# Sheet1.net
KiCad netlist of a schematic drawn in Altium Designer
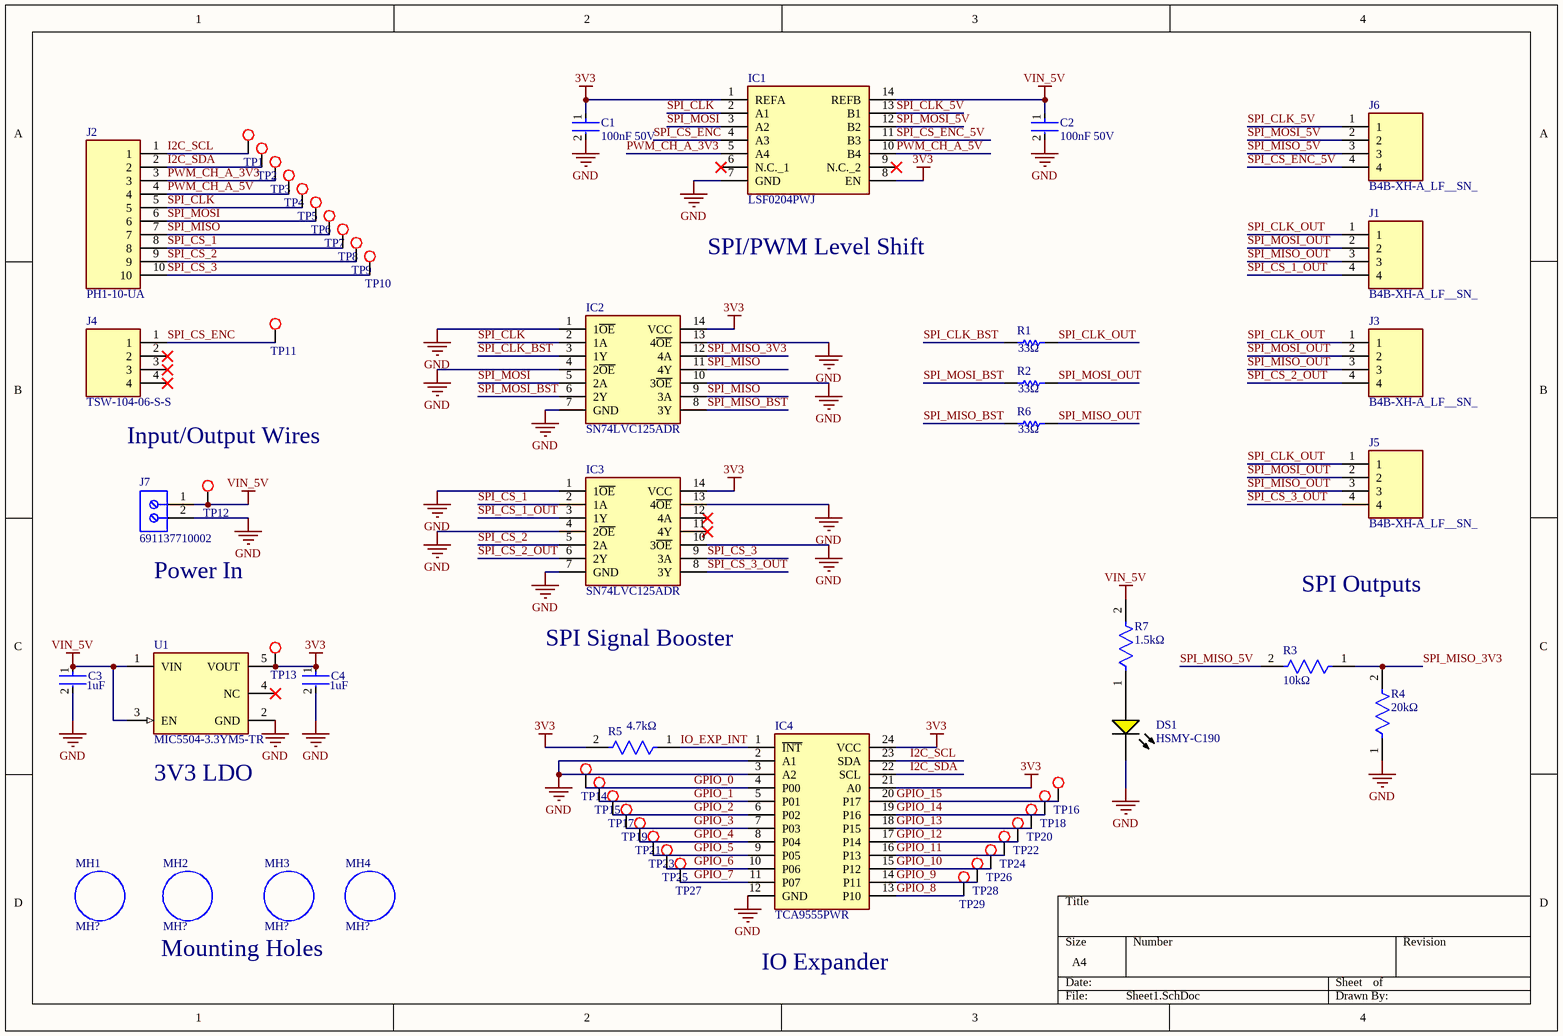
[diagram p0: Sheet1.SchDoc]

(export (version "E")
  (design (tool "Eeschema 10.0.6"))
  (components
    (comp (ref "C1")
      (value "100nF 50V")
      (footprint "FP-CL31-IPC_C")
      (description "Cap Ceramic 100nF 50V X7R ±10% SMD 1206 +125°C Embossed T/R")
      (fields (field (name "TOLERANCE") "10%"))
      (libsource (lib "Altium Content Vault") (part "b4654b650e69147ec39a6b967a45e02"))
    )
    (comp (ref "C2")
      (value "100nF 50V")
      (footprint "FP-CL31-IPC_C")
      (description "Cap Ceramic 100nF 50V X7R ±10% SMD 1206 +125°C Embossed T/R")
      (fields (field (name "TOLERANCE") "10%"))
      (libsource (lib "Altium Content Vault") (part "b4654b650e69147ec39a6b967a45e02"))
    )
    (comp (ref "C3")
      (value "1uF")
      (footprint "FP-CL10-IPC_C")
      (description "Cap Ceramic 1uF 10V X5R ±10% Pad SMD 0603 +85°C T/R")
      (fields (field (name "VOLTAGE") "10V") (field (name "TOLERANCE") "10%"))
      (libsource (lib "Altium Content Vault") (part "b4654b650e69147ec39a6b967a45e02"))
    )
    (comp (ref "C4")
      (value "1uF")
      (footprint "FP-CL10-IPC_C")
      (description "Cap Ceramic 1uF 10V X5R ±10% Pad SMD 0603 +85°C T/R")
      (fields (field (name "VOLTAGE") "10V") (field (name "TOLERANCE") "10%"))
      (libsource (lib "Altium Content Vault") (part "b4654b650e69147ec39a6b967a45e02"))
    )
    (comp (ref "DS1")
      (value "HSMY-C190")
      (footprint "AVAG-HSMX-C190_V")
      (description "LED Uni-Color Yellow, 65 mW, 20 mA, -40 to 85 degC, 2-Pin SMD, RoHS, Tape and Reel")
      (fields (field (name "TOLERANCE") "1%"))
      (libsource (lib "Altium Content Vault") (part "LED-YELLOW-AK-2"))
    )
    (comp (ref "IC1")
      (value "LSF0204PWJ")
      (footprint "SamacSys:SOP65P640X110-14N")
      (description "Integrated Circuit")
      (fields (field (name "MOUSER PART NUMBER") "771-LSF0204PWJ"))
      (libsource (lib "*") (part "LSF0204PWJ"))
    )
    (comp (ref "IC2")
      (value "SN74LVC125ADR")
      (footprint "SamacSys:SOIC127P600X175-14N")
      (description "Integrated Circuit")
      (fields (field (name "MOUSER PART NUMBER") "595-SN74LVC125ADR"))
      (libsource (lib "*") (part "SN74LVC125ADR"))
    )
    (comp (ref "IC3")
      (value "SN74LVC125ADR")
      (footprint "SamacSys:SOIC127P600X175-14N")
      (description "Integrated Circuit")
      (fields (field (name "MOUSER PART NUMBER") "595-SN74LVC125ADR"))
      (libsource (lib "*") (part "SN74LVC125ADR"))
    )
    (comp (ref "IC4")
      (value "TCA9555PWR")
      (footprint "SamacSys:SOP65P640X120-24N")
      (description "Integrated Circuit")
      (fields (field (name "MOUSER PART NUMBER") "595-TCA9555PWR"))
      (libsource (lib "*") (part "TCA9555PWR"))
    )
    (comp (ref "J1")
      (value "B4B-XH-A_LF__SN_")
      (footprint "SamacSys:B4BXHALFSN")
      (description "Connector")
      (fields
        (field (name "MANUFACTURER_PART_NUMBER") "B4B-XH-A(LF)(SN)")
        (field (name "MOUSER PART NUMBER") "306-B4BXHALFSN")
      )
      (libsource (lib "*") (part "B4B-XH-A_LF__SN_"))
    )
    (comp (ref "J2")
      (value "PH1-10-UA")
      (footprint "SamacSys:HDRV10W64P0X254_1X10_2540X249X886P")
      (description "Connector")
      (fields (field (name "MOUSER PART NUMBER") "737-PH1-10-UA"))
      (libsource (lib "*") (part "PH1-10-UA"))
    )
    (comp (ref "J3")
      (value "B4B-XH-A_LF__SN_")
      (footprint "SamacSys:B4BXHALFSN")
      (description "Connector")
      (fields
        (field (name "MANUFACTURER_PART_NUMBER") "B4B-XH-A(LF)(SN)")
        (field (name "MOUSER PART NUMBER") "306-B4BXHALFSN")
      )
      (libsource (lib "*") (part "B4B-XH-A_LF__SN_"))
    )
    (comp (ref "J4")
      (value "TSW-104-06-S-S")
      (footprint "SamacSys:TSW-104-XX-YY-S")
      (description "Connector")
      (libsource (lib "*") (part "TSW-104-06-S-S"))
    )
    (comp (ref "J5")
      (value "B4B-XH-A_LF__SN_")
      (footprint "SamacSys:B4BXHALFSN")
      (description "Connector")
      (fields
        (field (name "MANUFACTURER_PART_NUMBER") "B4B-XH-A(LF)(SN)")
        (field (name "MOUSER PART NUMBER") "306-B4BXHALFSN")
      )
      (libsource (lib "*") (part "B4B-XH-A_LF__SN_"))
    )
    (comp (ref "J6")
      (value "B4B-XH-A_LF__SN_")
      (footprint "SamacSys:B4BXHALFSN")
      (description "Connector")
      (fields
        (field (name "MANUFACTURER_PART_NUMBER") "B4B-XH-A(LF)(SN)")
        (field (name "MOUSER PART NUMBER") "306-B4BXHALFSN")
      )
      (libsource (lib "*") (part "B4B-XH-A_LF__SN_"))
    )
    (comp (ref "J7")
      (value "691137710002")
      (footprint "691137710002")
      (libsource (lib "Altium Content Vault") (part "TBL - 1R - 02P - Screw"))
    )
    (comp (ref "MH1")
      (value "MH?")
      (footprint "Mounting Hole")
      (libsource (lib "Schlib1") (part "Mounting Hole"))
    )
    (comp (ref "MH2")
      (value "MH?")
      (footprint "Mounting Hole")
      (libsource (lib "Schlib1") (part "Mounting Hole"))
    )
    (comp (ref "MH3")
      (value "MH?")
      (footprint "Mounting Hole")
      (libsource (lib "Schlib1") (part "Mounting Hole"))
    )
    (comp (ref "MH4")
      (value "MH?")
      (footprint "Mounting Hole")
      (libsource (lib "Schlib1") (part "Mounting Hole"))
    )
    (comp (ref "R1")
      (value "33Ω")
      (footprint "RESC1609X50X30NL10T20")
      (fields (field (name "MANUFACTURER") "Vishay Dale") (field (name "PART NUMBER") "CRCW060333R0JNTA"))
      (libsource (lib "Altium Content Vault") (part "RES"))
    )
    (comp (ref "R2")
      (value "33Ω")
      (footprint "RESC1609X50X30NL10T20")
      (fields (field (name "MANUFACTURER") "Vishay Dale") (field (name "PART NUMBER") "CRCW060333R0JNTA"))
      (libsource (lib "Altium Content Vault") (part "RES"))
    )
    (comp (ref "R3")
      (value "10kΩ")
      (footprint "FP-RT0603-MFG")
      (description "RES SMD 10K OHM 0.1% 1/10W 0603")
      (fields
        (field (name "TOLERANCE") "0.001")
        (field (name "OCTOPART") "https://octopart.com/rt0603bre0710kl-yageo-1273959")
      )
      (libsource (lib "Altium Content Vault") (part "1029c3af85768c4190bb7ad29bc67b5"))
    )
    (comp (ref "R4")
      (value "20kΩ")
      (footprint "FP-RT0805-MFG")
      (description "RES SMD 20K OHM 1% 1/8W 0805")
      (fields
        (field (name "MANUFACTURER") "Yageo")
        (field (name "MANUFACTURER PART NUMBER") "RT0805FRE0720KL")
      )
      (libsource (lib "Altium Content Vault") (part "1029c3af85768c4190bb7ad29bc67b5"))
    )
    (comp (ref "R5")
      (value "4.7kΩ")
      (footprint "FP-RT0805-MFG")
      (description "RES SMD 4.7K OHM 1% 1/8W 0805")
      (fields (field (name "TOLERANCE") "0.0001") (field (name "MANUFACTURER PART NUMBER") "RT0805FRE074K7L"))
      (libsource (lib "Altium Content Vault") (part "1029c3af85768c4190bb7ad29bc67b5"))
    )
    (comp (ref "R6")
      (value "33Ω")
      (footprint "RESC1609X50X30NL10T20")
      (fields (field (name "MANUFACTURER") "Vishay Dale") (field (name "PART NUMBER") "CRCW060333R0JNTA"))
      (libsource (lib "Altium Content Vault") (part "RES"))
    )
    (comp (ref "R7")
      (value "1.5kΩ")
      (footprint "FP-RC1608-IPC_B")
      (description "Res Thick Film 0603 1.5kΩ 1% 0.1W ±100ppm/°C Molded SMD T/R")
      (fields (field (name "TOLERANCE") "1%"))
      (libsource (lib "Altium Content Vault") (part "1029c3af85768c4190bb7ad29bc67b5"))
    )
    (comp (ref "TP1") (value "TP") (footprint "Testpoint") (libsource (lib "Schlib1") (part "Testpoint")))
    (comp (ref "TP2") (value "TP") (footprint "Testpoint") (libsource (lib "Schlib1") (part "Testpoint")))
    (comp (ref "TP3") (value "TP") (footprint "Testpoint") (libsource (lib "Schlib1") (part "Testpoint")))
    (comp (ref "TP4") (value "TP") (footprint "Testpoint") (libsource (lib "Schlib1") (part "Testpoint")))
    (comp (ref "TP5") (value "TP") (footprint "Testpoint") (libsource (lib "Schlib1") (part "Testpoint")))
    (comp (ref "TP6") (value "TP") (footprint "Testpoint") (libsource (lib "Schlib1") (part "Testpoint")))
    (comp (ref "TP7") (value "TP") (footprint "Testpoint") (libsource (lib "Schlib1") (part "Testpoint")))
    (comp (ref "TP8") (value "TP") (footprint "Testpoint") (libsource (lib "Schlib1") (part "Testpoint")))
    (comp (ref "TP9") (value "TP") (footprint "Testpoint") (libsource (lib "Schlib1") (part "Testpoint")))
    (comp (ref "TP10") (value "TP") (footprint "Testpoint") (libsource (lib "Schlib1") (part "Testpoint")))
    (comp (ref "TP11") (value "TP") (footprint "Testpoint") (libsource (lib "Schlib1") (part "Testpoint")))
    (comp (ref "TP12") (value "TP") (footprint "Testpoint") (libsource (lib "Schlib1") (part "Testpoint")))
    (comp (ref "TP13") (value "TP") (footprint "Testpoint") (libsource (lib "Schlib1") (part "Testpoint")))
    (comp (ref "TP14") (value "TP") (footprint "Testpoint") (libsource (lib "Schlib1") (part "Testpoint")))
    (comp (ref "TP15") (value "TP") (footprint "Testpoint") (libsource (lib "Schlib1") (part "Testpoint")))
    (comp (ref "TP16") (value "TP") (footprint "Testpoint") (libsource (lib "Schlib1") (part "Testpoint")))
    (comp (ref "TP17") (value "TP") (footprint "Testpoint") (libsource (lib "Schlib1") (part "Testpoint")))
    (comp (ref "TP18") (value "TP") (footprint "Testpoint") (libsource (lib "Schlib1") (part "Testpoint")))
    (comp (ref "TP19") (value "TP") (footprint "Testpoint") (libsource (lib "Schlib1") (part "Testpoint")))
    (comp (ref "TP20") (value "TP") (footprint "Testpoint") (libsource (lib "Schlib1") (part "Testpoint")))
    (comp (ref "TP21") (value "TP") (footprint "Testpoint") (libsource (lib "Schlib1") (part "Testpoint")))
    (comp (ref "TP22") (value "TP") (footprint "Testpoint") (libsource (lib "Schlib1") (part "Testpoint")))
    (comp (ref "TP23") (value "TP") (footprint "Testpoint") (libsource (lib "Schlib1") (part "Testpoint")))
    (comp (ref "TP24") (value "TP") (footprint "Testpoint") (libsource (lib "Schlib1") (part "Testpoint")))
    (comp (ref "TP25") (value "TP") (footprint "Testpoint") (libsource (lib "Schlib1") (part "Testpoint")))
    (comp (ref "TP26") (value "TP") (footprint "Testpoint") (libsource (lib "Schlib1") (part "Testpoint")))
    (comp (ref "TP27") (value "TP") (footprint "Testpoint") (libsource (lib "Schlib1") (part "Testpoint")))
    (comp (ref "TP28") (value "TP") (footprint "Testpoint") (libsource (lib "Schlib1") (part "Testpoint")))
    (comp (ref "TP29") (value "TP") (footprint "Testpoint") (libsource (lib "Schlib1") (part "Testpoint")))
    (comp (ref "U1")
      (value "MIC5504-3.3YM5-TR")
      (footprint "FP-SOT23-5LD-PL-1-MFG")
      (description "IC REG LINEAR 3.3V 300MA SOT23-5")
      (libsource (lib "Altium Content Vault") (part "96048095611b4a9579e1e315950d302"))
    )
  )
  (nets
    (net (code "1") (name "/GPIO_0") (class "Default")
      (node (ref "IC4") (pin "4") (pinfunction "P00_4") (pintype "passive"))
      (node (ref "TP14") (pin "0") (pinfunction "0_0") (pintype "passive"))
    )
    (net (code "2") (name "/GPIO_1") (class "Default")
      (node (ref "IC4") (pin "5") (pinfunction "P01_5") (pintype "passive"))
      (node (ref "TP15") (pin "0") (pinfunction "0_0") (pintype "passive"))
    )
    (net (code "3") (name "/GPIO_2") (class "Default")
      (node (ref "IC4") (pin "6") (pinfunction "P02_6") (pintype "passive"))
      (node (ref "TP17") (pin "0") (pinfunction "0_0") (pintype "passive"))
    )
    (net (code "4") (name "/GPIO_3") (class "Default")
      (node (ref "IC4") (pin "7") (pinfunction "P03_7") (pintype "passive"))
      (node (ref "TP19") (pin "0") (pinfunction "0_0") (pintype "passive"))
    )
    (net (code "5") (name "/GPIO_4") (class "Default")
      (node (ref "IC4") (pin "8") (pinfunction "P04_8") (pintype "passive"))
      (node (ref "TP21") (pin "0") (pinfunction "0_0") (pintype "passive"))
    )
    (net (code "6") (name "/GPIO_5") (class "Default")
      (node (ref "IC4") (pin "9") (pinfunction "P05_9") (pintype "passive"))
      (node (ref "TP23") (pin "0") (pinfunction "0_0") (pintype "passive"))
    )
    (net (code "7") (name "/GPIO_6") (class "Default")
      (node (ref "IC4") (pin "10") (pinfunction "P06_10") (pintype "passive"))
      (node (ref "TP25") (pin "0") (pinfunction "0_0") (pintype "passive"))
    )
    (net (code "8") (name "/GPIO_7") (class "Default")
      (node (ref "IC4") (pin "11") (pinfunction "P07_11") (pintype "passive"))
      (node (ref "TP27") (pin "0") (pinfunction "0_0") (pintype "passive"))
    )
    (net (code "9") (name "/GPIO_8") (class "Default")
      (node (ref "IC4") (pin "13") (pinfunction "P10_13") (pintype "passive"))
      (node (ref "TP29") (pin "0") (pinfunction "0_0") (pintype "passive"))
    )
    (net (code "10") (name "/GPIO_9") (class "Default")
      (node (ref "IC4") (pin "14") (pinfunction "P11_14") (pintype "passive"))
      (node (ref "TP28") (pin "0") (pinfunction "0_0") (pintype "passive"))
    )
    (net (code "11") (name "/GPIO_10") (class "Default")
      (node (ref "IC4") (pin "15") (pinfunction "P12_15") (pintype "passive"))
      (node (ref "TP26") (pin "0") (pinfunction "0_0") (pintype "passive"))
    )
    (net (code "12") (name "/GPIO_11") (class "Default")
      (node (ref "IC4") (pin "16") (pinfunction "P13_16") (pintype "passive"))
      (node (ref "TP24") (pin "0") (pinfunction "0_0") (pintype "passive"))
    )
    (net (code "13") (name "/GPIO_12") (class "Default")
      (node (ref "IC4") (pin "17") (pinfunction "P14_17") (pintype "passive"))
      (node (ref "TP22") (pin "0") (pinfunction "0_0") (pintype "passive"))
    )
    (net (code "14") (name "/GPIO_13") (class "Default")
      (node (ref "IC4") (pin "18") (pinfunction "P15_18") (pintype "passive"))
      (node (ref "TP20") (pin "0") (pinfunction "0_0") (pintype "passive"))
    )
    (net (code "15") (name "/GPIO_14") (class "Default")
      (node (ref "IC4") (pin "19") (pinfunction "P16_19") (pintype "passive"))
      (node (ref "TP18") (pin "0") (pinfunction "0_0") (pintype "passive"))
    )
    (net (code "16") (name "/GPIO_15") (class "Default")
      (node (ref "IC4") (pin "20") (pinfunction "P17_20") (pintype "passive"))
      (node (ref "TP16") (pin "0") (pinfunction "0_0") (pintype "passive"))
    )
    (net (code "17") (name "/I2C_SCL") (class "Default")
      (node (ref "IC4") (pin "23") (pinfunction "SDA_23") (pintype "passive"))
      (node (ref "J2") (pin "1") (pinfunction "1_1") (pintype "passive"))
      (node (ref "TP1") (pin "0") (pinfunction "0_0") (pintype "passive"))
    )
    (net (code "18") (name "/I2C_SDA") (class "Default")
      (node (ref "IC4") (pin "22") (pinfunction "SCL_22") (pintype "passive"))
      (node (ref "J2") (pin "2") (pinfunction "2_2") (pintype "passive"))
      (node (ref "TP2") (pin "0") (pinfunction "0_0") (pintype "passive"))
    )
    (net (code "19") (name "/IO_EXP_INT") (class "Default")
      (node (ref "IC4") (pin "1") (pinfunction "~{INT}_1") (pintype "passive"))
      (node (ref "R5") (pin "1") (pinfunction "1_1") (pintype "passive"))
    )
    (net (code "20") (name "/PWM_CH_A_3V3") (class "Default")
      (node (ref "IC1") (pin "5") (pinfunction "A4_5") (pintype "passive"))
      (node (ref "J2") (pin "3") (pinfunction "3_3") (pintype "passive"))
      (node (ref "TP3") (pin "0") (pinfunction "0_0") (pintype "passive"))
    )
    (net (code "21") (name "/PWM_CH_A_5V") (class "Default")
      (node (ref "IC1") (pin "10") (pinfunction "B4_10") (pintype "passive"))
      (node (ref "J2") (pin "4") (pinfunction "4_4") (pintype "passive"))
      (node (ref "TP4") (pin "0") (pinfunction "0_0") (pintype "passive"))
    )
    (net (code "22") (name "/SPI_CLK") (class "Default")
      (node (ref "IC1") (pin "2") (pinfunction "A1_2") (pintype "passive"))
      (node (ref "IC2") (pin "2") (pinfunction "1A_2") (pintype "passive"))
      (node (ref "J2") (pin "5") (pinfunction "5_5") (pintype "passive"))
      (node (ref "TP5") (pin "0") (pinfunction "0_0") (pintype "passive"))
    )
    (net (code "23") (name "/SPI_CLK_5V") (class "Default")
      (node (ref "IC1") (pin "13") (pinfunction "B1_13") (pintype "passive"))
      (node (ref "J6") (pin "1") (pinfunction "1_1") (pintype "passive"))
    )
    (net (code "24") (name "/SPI_CLK_BST") (class "Default")
      (node (ref "IC2") (pin "3") (pinfunction "1Y_3") (pintype "passive"))
      (node (ref "R1") (pin "1") (pinfunction "1_1") (pintype "passive"))
    )
    (net (code "25") (name "/SPI_CLK_OUT") (class "Default")
      (node (ref "J1") (pin "1") (pinfunction "1_1") (pintype "passive"))
      (node (ref "J3") (pin "1") (pinfunction "1_1") (pintype "passive"))
      (node (ref "J5") (pin "1") (pinfunction "1_1") (pintype "passive"))
      (node (ref "R1") (pin "2") (pinfunction "2_2") (pintype "passive"))
    )
    (net (code "26") (name "/SPI_CS_1") (class "Default")
      (node (ref "IC3") (pin "2") (pinfunction "1A_2") (pintype "passive"))
      (node (ref "J2") (pin "8") (pinfunction "8_8") (pintype "passive"))
      (node (ref "TP8") (pin "0") (pinfunction "0_0") (pintype "passive"))
    )
    (net (code "27") (name "/SPI_CS_1_OUT") (class "Default")
      (node (ref "IC3") (pin "3") (pinfunction "1Y_3") (pintype "passive"))
      (node (ref "J1") (pin "4") (pinfunction "4_4") (pintype "passive"))
    )
    (net (code "28") (name "/SPI_CS_2") (class "Default")
      (node (ref "IC3") (pin "5") (pinfunction "2A_5") (pintype "passive"))
      (node (ref "J2") (pin "9") (pinfunction "9_9") (pintype "passive"))
      (node (ref "TP9") (pin "0") (pinfunction "0_0") (pintype "passive"))
    )
    (net (code "29") (name "/SPI_CS_2_OUT") (class "Default")
      (node (ref "IC3") (pin "6") (pinfunction "2Y_6") (pintype "passive"))
      (node (ref "J3") (pin "4") (pinfunction "4_4") (pintype "passive"))
    )
    (net (code "30") (name "/SPI_CS_3") (class "Default")
      (node (ref "IC3") (pin "9") (pinfunction "3A_9") (pintype "passive"))
      (node (ref "J2") (pin "10") (pinfunction "10_10") (pintype "passive"))
      (node (ref "TP10") (pin "0") (pinfunction "0_0") (pintype "passive"))
    )
    (net (code "31") (name "/SPI_CS_3_OUT") (class "Default")
      (node (ref "IC3") (pin "8") (pinfunction "3Y_8") (pintype "passive"))
      (node (ref "J5") (pin "4") (pinfunction "4_4") (pintype "passive"))
    )
    (net (code "32") (name "/SPI_CS_ENC") (class "Default")
      (node (ref "IC1") (pin "4") (pinfunction "A3_4") (pintype "passive"))
      (node (ref "J4") (pin "1") (pinfunction "1_1") (pintype "passive"))
      (node (ref "TP11") (pin "0") (pinfunction "0_0") (pintype "passive"))
    )
    (net (code "33") (name "/SPI_CS_ENC_5V") (class "Default")
      (node (ref "IC1") (pin "11") (pinfunction "B3_11") (pintype "passive"))
      (node (ref "J6") (pin "4") (pinfunction "4_4") (pintype "passive"))
    )
    (net (code "34") (name "/SPI_MISO") (class "Default")
      (node (ref "IC2") (pin "11") (pinfunction "4Y_11") (pintype "passive"))
      (node (ref "IC2") (pin "9") (pinfunction "3A_9") (pintype "passive"))
      (node (ref "J2") (pin "7") (pinfunction "7_7") (pintype "passive"))
      (node (ref "TP7") (pin "0") (pinfunction "0_0") (pintype "passive"))
    )
    (net (code "35") (name "/SPI_MISO_3V3") (class "Default")
      (node (ref "IC2") (pin "12") (pinfunction "4A_12") (pintype "passive"))
      (node (ref "R3") (pin "1") (pinfunction "1_1") (pintype "passive"))
      (node (ref "R4") (pin "2") (pinfunction "2_2") (pintype "passive"))
    )
    (net (code "36") (name "/SPI_MISO_5V") (class "Default")
      (node (ref "J6") (pin "3") (pinfunction "3_3") (pintype "passive"))
      (node (ref "R3") (pin "2") (pinfunction "2_2") (pintype "passive"))
    )
    (net (code "37") (name "/SPI_MISO_BST") (class "Default")
      (node (ref "IC2") (pin "8") (pinfunction "3Y_8") (pintype "passive"))
      (node (ref "R6") (pin "1") (pinfunction "1_1") (pintype "passive"))
    )
    (net (code "38") (name "/SPI_MISO_OUT") (class "Default")
      (node (ref "J1") (pin "3") (pinfunction "3_3") (pintype "passive"))
      (node (ref "J3") (pin "3") (pinfunction "3_3") (pintype "passive"))
      (node (ref "J5") (pin "3") (pinfunction "3_3") (pintype "passive"))
      (node (ref "R6") (pin "2") (pinfunction "2_2") (pintype "passive"))
    )
    (net (code "39") (name "/SPI_MOSI") (class "Default")
      (node (ref "IC1") (pin "3") (pinfunction "A2_3") (pintype "passive"))
      (node (ref "IC2") (pin "5") (pinfunction "2A_5") (pintype "passive"))
      (node (ref "J2") (pin "6") (pinfunction "6_6") (pintype "passive"))
      (node (ref "TP6") (pin "0") (pinfunction "0_0") (pintype "passive"))
    )
    (net (code "40") (name "/SPI_MOSI_5V") (class "Default")
      (node (ref "IC1") (pin "12") (pinfunction "B2_12") (pintype "passive"))
      (node (ref "J6") (pin "2") (pinfunction "2_2") (pintype "passive"))
    )
    (net (code "41") (name "/SPI_MOSI_BST") (class "Default")
      (node (ref "IC2") (pin "6") (pinfunction "2Y_6") (pintype "passive"))
      (node (ref "R2") (pin "1") (pinfunction "1_1") (pintype "passive"))
    )
    (net (code "42") (name "/SPI_MOSI_OUT") (class "Default")
      (node (ref "J1") (pin "2") (pinfunction "2_2") (pintype "passive"))
      (node (ref "J3") (pin "2") (pinfunction "2_2") (pintype "passive"))
      (node (ref "J5") (pin "2") (pinfunction "2_2") (pintype "passive"))
      (node (ref "R2") (pin "2") (pinfunction "2_2") (pintype "passive"))
    )
    (net (code "43") (name "3V3") (class "Default")
      (node (ref "C1") (pin "1") (pinfunction "1_1") (pintype "passive"))
      (node (ref "C4") (pin "1") (pinfunction "1_1") (pintype "passive"))
      (node (ref "IC1") (pin "1") (pinfunction "REFA_1") (pintype "passive"))
      (node (ref "IC1") (pin "8") (pinfunction "EN_8") (pintype "passive"))
      (node (ref "IC2") (pin "14") (pinfunction "VCC_14") (pintype "passive"))
      (node (ref "IC3") (pin "14") (pinfunction "VCC_14") (pintype "passive"))
      (node (ref "IC4") (pin "21") (pinfunction "A0_21") (pintype "passive"))
      (node (ref "IC4") (pin "24") (pinfunction "VCC_24") (pintype "passive"))
      (node (ref "R5") (pin "2") (pinfunction "2_2") (pintype "passive"))
      (node (ref "TP13") (pin "0") (pinfunction "0_0") (pintype "passive"))
      (node (ref "U1") (pin "5") (pinfunction "VOUT_5") (pintype "power_in"))
    )
    (net (code "44") (name "GND") (class "Default")
      (node (ref "C1") (pin "2") (pinfunction "2_2") (pintype "passive"))
      (node (ref "C2") (pin "2") (pinfunction "2_2") (pintype "passive"))
      (node (ref "C3") (pin "2") (pinfunction "2_2") (pintype "passive"))
      (node (ref "C4") (pin "2") (pinfunction "2_2") (pintype "passive"))
      (node (ref "DS1") (pin "2") (pinfunction "K_2") (pintype "passive"))
      (node (ref "IC1") (pin "7") (pinfunction "GND_7") (pintype "passive"))
      (node (ref "IC2") (pin "1") (pinfunction "1~{OE}_1") (pintype "passive"))
      (node (ref "IC2") (pin "10") (pinfunction "3~{OE}_10") (pintype "passive"))
      (node (ref "IC2") (pin "13") (pinfunction "4~{OE}_13") (pintype "passive"))
      (node (ref "IC2") (pin "4") (pinfunction "2~{OE}_4") (pintype "passive"))
      (node (ref "IC2") (pin "7") (pinfunction "GND_7") (pintype "passive"))
      (node (ref "IC3") (pin "1") (pinfunction "1~{OE}_1") (pintype "passive"))
      (node (ref "IC3") (pin "10") (pinfunction "3~{OE}_10") (pintype "passive"))
      (node (ref "IC3") (pin "13") (pinfunction "4~{OE}_13") (pintype "passive"))
      (node (ref "IC3") (pin "4") (pinfunction "2~{OE}_4") (pintype "passive"))
      (node (ref "IC3") (pin "7") (pinfunction "GND_7") (pintype "passive"))
      (node (ref "IC4") (pin "12") (pinfunction "GND_12") (pintype "passive"))
      (node (ref "IC4") (pin "2") (pinfunction "A1_2") (pintype "passive"))
      (node (ref "IC4") (pin "3") (pinfunction "A2_3") (pintype "passive"))
      (node (ref "J7") (pin "2") (pinfunction "2_2") (pintype "passive"))
      (node (ref "R4") (pin "1") (pinfunction "1_1") (pintype "passive"))
      (node (ref "U1") (pin "2") (pinfunction "GND_2") (pintype "power_in"))
    )
    (net (code "45") (name "Net-(DS1-A)") (class "Default")
      (node (ref "DS1") (pin "1") (pinfunction "A_1") (pintype "passive"))
      (node (ref "R7") (pin "1") (pinfunction "1_1") (pintype "passive"))
    )
    (net (code "46") (name "VIN_5V") (class "Default")
      (node (ref "C2") (pin "1") (pinfunction "1_1") (pintype "passive"))
      (node (ref "C3") (pin "1") (pinfunction "1_1") (pintype "passive"))
      (node (ref "IC1") (pin "14") (pinfunction "REFB_14") (pintype "passive"))
      (node (ref "J7") (pin "1") (pinfunction "1_1") (pintype "passive"))
      (node (ref "R7") (pin "2") (pinfunction "2_2") (pintype "passive"))
      (node (ref "TP12") (pin "0") (pinfunction "0_0") (pintype "passive"))
      (node (ref "U1") (pin "1") (pinfunction "VIN_1") (pintype "power_in"))
      (node (ref "U1") (pin "3") (pinfunction "EN_3") (pintype "input"))
    )
    (net (code "47") (name "unconnected-(IC1-N.C._1-Pad6)") (class "Default")
      (node (ref "IC1") (pin "6") (pinfunction "N.C._1_6") (pintype "passive+no_connect"))
    )
    (net (code "48") (name "unconnected-(IC1-N.C._2-Pad9)") (class "Default")
      (node (ref "IC1") (pin "9") (pinfunction "N.C._2_9") (pintype "passive+no_connect"))
    )
    (net (code "49") (name "unconnected-(IC3-4A-Pad12)") (class "Default")
      (node (ref "IC3") (pin "12") (pinfunction "4A_12") (pintype "passive+no_connect"))
    )
    (net (code "50") (name "unconnected-(IC3-4Y-Pad11)") (class "Default")
      (node (ref "IC3") (pin "11") (pinfunction "4Y_11") (pintype "passive+no_connect"))
    )
    (net (code "51") (name "unconnected-(J4-Pad2)") (class "Default")
      (node (ref "J4") (pin "2") (pinfunction "2_2") (pintype "passive+no_connect"))
    )
    (net (code "52") (name "unconnected-(J4-Pad3)") (class "Default")
      (node (ref "J4") (pin "3") (pinfunction "3_3") (pintype "passive+no_connect"))
    )
    (net (code "53") (name "unconnected-(J4-Pad4)") (class "Default")
      (node (ref "J4") (pin "4") (pinfunction "4_4") (pintype "passive+no_connect"))
    )
    (net (code "54") (name "unconnected-(U1-NC-Pad4)") (class "Default")
      (node (ref "U1") (pin "4") (pinfunction "NC_4") (pintype "passive+no_connect"))
    )
  )
)
